# 8bitPig-PigstyGates-FrontPCB.net
KiCad netlist of a schematic drawn in EAGLE
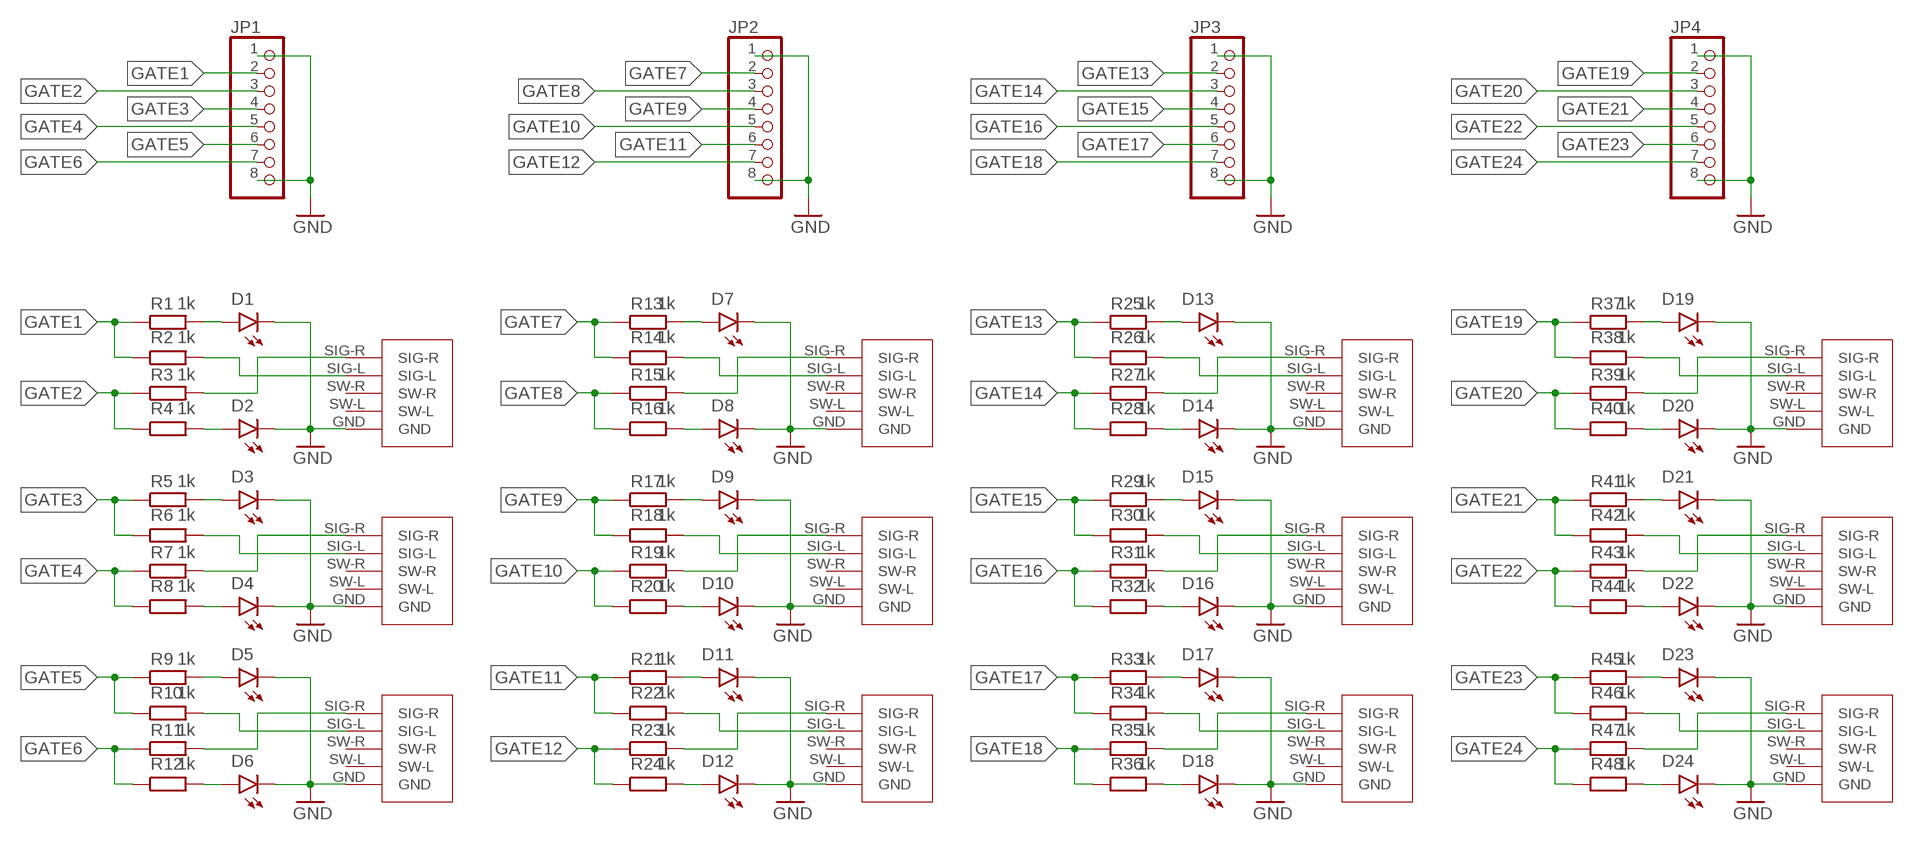
[diagram p0: schematic, sheet 1]

(export (version "E")
  (design (tool "Eeschema 10.0.6"))
  (components
    (comp (ref "D1")
      (value "LED3MM")
      (footprint "eagle-import:LED_3MM")
      (libsource (lib "eagle-import") (part "LED3MM"))
    )
    (comp (ref "D2")
      (value "LED3MM")
      (footprint "eagle-import:LED_3MM")
      (libsource (lib "eagle-import") (part "LED3MM"))
    )
    (comp (ref "D3")
      (value "LED3MM")
      (footprint "eagle-import:LED_3MM")
      (libsource (lib "eagle-import") (part "LED3MM"))
    )
    (comp (ref "D4")
      (value "LED3MM")
      (footprint "eagle-import:LED_3MM")
      (libsource (lib "eagle-import") (part "LED3MM"))
    )
    (comp (ref "D5")
      (value "LED3MM")
      (footprint "eagle-import:LED_3MM")
      (libsource (lib "eagle-import") (part "LED3MM"))
    )
    (comp (ref "D6")
      (value "LED3MM")
      (footprint "eagle-import:LED_3MM")
      (libsource (lib "eagle-import") (part "LED3MM"))
    )
    (comp (ref "D7")
      (value "LED3MM")
      (footprint "eagle-import:LED_3MM")
      (libsource (lib "eagle-import") (part "LED3MM"))
    )
    (comp (ref "D8")
      (value "LED3MM")
      (footprint "eagle-import:LED_3MM")
      (libsource (lib "eagle-import") (part "LED3MM"))
    )
    (comp (ref "D9")
      (value "LED3MM")
      (footprint "eagle-import:LED_3MM")
      (libsource (lib "eagle-import") (part "LED3MM"))
    )
    (comp (ref "D10")
      (value "LED3MM")
      (footprint "eagle-import:LED_3MM")
      (libsource (lib "eagle-import") (part "LED3MM"))
    )
    (comp (ref "D11")
      (value "LED3MM")
      (footprint "eagle-import:LED_3MM")
      (libsource (lib "eagle-import") (part "LED3MM"))
    )
    (comp (ref "D12")
      (value "LED3MM")
      (footprint "eagle-import:LED_3MM")
      (libsource (lib "eagle-import") (part "LED3MM"))
    )
    (comp (ref "D13")
      (value "LED3MM")
      (footprint "eagle-import:LED_3MM")
      (libsource (lib "eagle-import") (part "LED3MM"))
    )
    (comp (ref "D14")
      (value "LED3MM")
      (footprint "eagle-import:LED_3MM")
      (libsource (lib "eagle-import") (part "LED3MM"))
    )
    (comp (ref "D15")
      (value "LED3MM")
      (footprint "eagle-import:LED_3MM")
      (libsource (lib "eagle-import") (part "LED3MM"))
    )
    (comp (ref "D16")
      (value "LED3MM")
      (footprint "eagle-import:LED_3MM")
      (libsource (lib "eagle-import") (part "LED3MM"))
    )
    (comp (ref "D17")
      (value "LED3MM")
      (footprint "eagle-import:LED_3MM")
      (libsource (lib "eagle-import") (part "LED3MM"))
    )
    (comp (ref "D18")
      (value "LED3MM")
      (footprint "eagle-import:LED_3MM")
      (libsource (lib "eagle-import") (part "LED3MM"))
    )
    (comp (ref "D19")
      (value "LED3MM")
      (footprint "eagle-import:LED_3MM")
      (libsource (lib "eagle-import") (part "LED3MM"))
    )
    (comp (ref "D20")
      (value "LED3MM")
      (footprint "eagle-import:LED_3MM")
      (libsource (lib "eagle-import") (part "LED3MM"))
    )
    (comp (ref "D21")
      (value "LED3MM")
      (footprint "eagle-import:LED_3MM")
      (libsource (lib "eagle-import") (part "LED3MM"))
    )
    (comp (ref "D22")
      (value "LED3MM")
      (footprint "eagle-import:LED_3MM")
      (libsource (lib "eagle-import") (part "LED3MM"))
    )
    (comp (ref "D23")
      (value "LED3MM")
      (footprint "eagle-import:LED_3MM")
      (libsource (lib "eagle-import") (part "LED3MM"))
    )
    (comp (ref "D24")
      (value "LED3MM")
      (footprint "eagle-import:LED_3MM")
      (libsource (lib "eagle-import") (part "LED3MM"))
    )
    (comp (ref "DUAL_JACK_1")
      (value "DUAL_MONO_THONKICONN")
      (footprint "eagle-import:DUAL_THONKICONN_MONO")
      (libsource (lib "eagle-import") (part "DUAL_MONO_THONKICONN"))
    )
    (comp (ref "DUAL_JACK_2")
      (value "DUAL_MONO_THONKICONN")
      (footprint "eagle-import:DUAL_THONKICONN_MONO")
      (libsource (lib "eagle-import") (part "DUAL_MONO_THONKICONN"))
    )
    (comp (ref "DUAL_JACK_3")
      (value "DUAL_MONO_THONKICONN")
      (footprint "eagle-import:DUAL_THONKICONN_MONO")
      (libsource (lib "eagle-import") (part "DUAL_MONO_THONKICONN"))
    )
    (comp (ref "DUAL_JACK_4")
      (value "DUAL_MONO_THONKICONN")
      (footprint "eagle-import:DUAL_THONKICONN_MONO")
      (libsource (lib "eagle-import") (part "DUAL_MONO_THONKICONN"))
    )
    (comp (ref "DUAL_JACK_5")
      (value "DUAL_MONO_THONKICONN")
      (footprint "eagle-import:DUAL_THONKICONN_MONO")
      (libsource (lib "eagle-import") (part "DUAL_MONO_THONKICONN"))
    )
    (comp (ref "DUAL_JACK_6")
      (value "DUAL_MONO_THONKICONN")
      (footprint "eagle-import:DUAL_THONKICONN_MONO")
      (libsource (lib "eagle-import") (part "DUAL_MONO_THONKICONN"))
    )
    (comp (ref "DUAL_JACK_7")
      (value "DUAL_MONO_THONKICONN")
      (footprint "eagle-import:DUAL_THONKICONN_MONO")
      (libsource (lib "eagle-import") (part "DUAL_MONO_THONKICONN"))
    )
    (comp (ref "DUAL_JACK_8")
      (value "DUAL_MONO_THONKICONN")
      (footprint "eagle-import:DUAL_THONKICONN_MONO")
      (libsource (lib "eagle-import") (part "DUAL_MONO_THONKICONN"))
    )
    (comp (ref "DUAL_JACK_9")
      (value "DUAL_MONO_THONKICONN")
      (footprint "eagle-import:DUAL_THONKICONN_MONO")
      (libsource (lib "eagle-import") (part "DUAL_MONO_THONKICONN"))
    )
    (comp (ref "DUAL_JACK_10")
      (value "DUAL_MONO_THONKICONN")
      (footprint "eagle-import:DUAL_THONKICONN_MONO")
      (libsource (lib "eagle-import") (part "DUAL_MONO_THONKICONN"))
    )
    (comp (ref "DUAL_JACK_11")
      (value "DUAL_MONO_THONKICONN")
      (footprint "eagle-import:DUAL_THONKICONN_MONO")
      (libsource (lib "eagle-import") (part "DUAL_MONO_THONKICONN"))
    )
    (comp (ref "DUAL_JACK_12")
      (value "DUAL_MONO_THONKICONN")
      (footprint "eagle-import:DUAL_THONKICONN_MONO")
      (libsource (lib "eagle-import") (part "DUAL_MONO_THONKICONN"))
    )
    (comp (ref "JP1")
      (value "PINHD-1X8")
      (footprint "eagle-import:1X08")
      (libsource (lib "eagle-import") (part "PINHD-1X8"))
    )
    (comp (ref "JP2")
      (value "PINHD-1X8")
      (footprint "eagle-import:1X08")
      (libsource (lib "eagle-import") (part "PINHD-1X8"))
    )
    (comp (ref "JP3")
      (value "PINHD-1X8")
      (footprint "eagle-import:1X08")
      (libsource (lib "eagle-import") (part "PINHD-1X8"))
    )
    (comp (ref "JP4")
      (value "PINHD-1X8")
      (footprint "eagle-import:1X08")
      (libsource (lib "eagle-import") (part "PINHD-1X8"))
    )
    (comp (ref "R1")
      (value "1k")
      (footprint "eagle-import:R0603")
      (libsource (lib "eagle-import") (part "R-EU_R0603"))
    )
    (comp (ref "R2")
      (value "1k")
      (footprint "eagle-import:R0603")
      (libsource (lib "eagle-import") (part "R-EU_R0603"))
    )
    (comp (ref "R3")
      (value "1k")
      (footprint "eagle-import:R0603")
      (libsource (lib "eagle-import") (part "R-EU_R0603"))
    )
    (comp (ref "R4")
      (value "1k")
      (footprint "eagle-import:R0603")
      (libsource (lib "eagle-import") (part "R-EU_R0603"))
    )
    (comp (ref "R5")
      (value "1k")
      (footprint "eagle-import:R0603")
      (libsource (lib "eagle-import") (part "R-EU_R0603"))
    )
    (comp (ref "R6")
      (value "1k")
      (footprint "eagle-import:R0603")
      (libsource (lib "eagle-import") (part "R-EU_R0603"))
    )
    (comp (ref "R7")
      (value "1k")
      (footprint "eagle-import:R0603")
      (libsource (lib "eagle-import") (part "R-EU_R0603"))
    )
    (comp (ref "R8")
      (value "1k")
      (footprint "eagle-import:R0603")
      (libsource (lib "eagle-import") (part "R-EU_R0603"))
    )
    (comp (ref "R9")
      (value "1k")
      (footprint "eagle-import:R0603")
      (libsource (lib "eagle-import") (part "R-EU_R0603"))
    )
    (comp (ref "R10")
      (value "1k")
      (footprint "eagle-import:R0603")
      (libsource (lib "eagle-import") (part "R-EU_R0603"))
    )
    (comp (ref "R11")
      (value "1k")
      (footprint "eagle-import:R0603")
      (libsource (lib "eagle-import") (part "R-EU_R0603"))
    )
    (comp (ref "R12")
      (value "1k")
      (footprint "eagle-import:R0603")
      (libsource (lib "eagle-import") (part "R-EU_R0603"))
    )
    (comp (ref "R13")
      (value "1k")
      (footprint "eagle-import:R0603")
      (libsource (lib "eagle-import") (part "R-EU_R0603"))
    )
    (comp (ref "R14")
      (value "1k")
      (footprint "eagle-import:R0603")
      (libsource (lib "eagle-import") (part "R-EU_R0603"))
    )
    (comp (ref "R15")
      (value "1k")
      (footprint "eagle-import:R0603")
      (libsource (lib "eagle-import") (part "R-EU_R0603"))
    )
    (comp (ref "R16")
      (value "1k")
      (footprint "eagle-import:R0603")
      (libsource (lib "eagle-import") (part "R-EU_R0603"))
    )
    (comp (ref "R17")
      (value "1k")
      (footprint "eagle-import:R0603")
      (libsource (lib "eagle-import") (part "R-EU_R0603"))
    )
    (comp (ref "R18")
      (value "1k")
      (footprint "eagle-import:R0603")
      (libsource (lib "eagle-import") (part "R-EU_R0603"))
    )
    (comp (ref "R19")
      (value "1k")
      (footprint "eagle-import:R0603")
      (libsource (lib "eagle-import") (part "R-EU_R0603"))
    )
    (comp (ref "R20")
      (value "1k")
      (footprint "eagle-import:R0603")
      (libsource (lib "eagle-import") (part "R-EU_R0603"))
    )
    (comp (ref "R21")
      (value "1k")
      (footprint "eagle-import:R0603")
      (libsource (lib "eagle-import") (part "R-EU_R0603"))
    )
    (comp (ref "R22")
      (value "1k")
      (footprint "eagle-import:R0603")
      (libsource (lib "eagle-import") (part "R-EU_R0603"))
    )
    (comp (ref "R23")
      (value "1k")
      (footprint "eagle-import:R0603")
      (libsource (lib "eagle-import") (part "R-EU_R0603"))
    )
    (comp (ref "R24")
      (value "1k")
      (footprint "eagle-import:R0603")
      (libsource (lib "eagle-import") (part "R-EU_R0603"))
    )
    (comp (ref "R25")
      (value "1k")
      (footprint "eagle-import:R0603")
      (libsource (lib "eagle-import") (part "R-EU_R0603"))
    )
    (comp (ref "R26")
      (value "1k")
      (footprint "eagle-import:R0603")
      (libsource (lib "eagle-import") (part "R-EU_R0603"))
    )
    (comp (ref "R27")
      (value "1k")
      (footprint "eagle-import:R0603")
      (libsource (lib "eagle-import") (part "R-EU_R0603"))
    )
    (comp (ref "R28")
      (value "1k")
      (footprint "eagle-import:R0603")
      (libsource (lib "eagle-import") (part "R-EU_R0603"))
    )
    (comp (ref "R29")
      (value "1k")
      (footprint "eagle-import:R0603")
      (libsource (lib "eagle-import") (part "R-EU_R0603"))
    )
    (comp (ref "R30")
      (value "1k")
      (footprint "eagle-import:R0603")
      (libsource (lib "eagle-import") (part "R-EU_R0603"))
    )
    (comp (ref "R31")
      (value "1k")
      (footprint "eagle-import:R0603")
      (libsource (lib "eagle-import") (part "R-EU_R0603"))
    )
    (comp (ref "R32")
      (value "1k")
      (footprint "eagle-import:R0603")
      (libsource (lib "eagle-import") (part "R-EU_R0603"))
    )
    (comp (ref "R33")
      (value "1k")
      (footprint "eagle-import:R0603")
      (libsource (lib "eagle-import") (part "R-EU_R0603"))
    )
    (comp (ref "R34")
      (value "1k")
      (footprint "eagle-import:R0603")
      (libsource (lib "eagle-import") (part "R-EU_R0603"))
    )
    (comp (ref "R35")
      (value "1k")
      (footprint "eagle-import:R0603")
      (libsource (lib "eagle-import") (part "R-EU_R0603"))
    )
    (comp (ref "R36")
      (value "1k")
      (footprint "eagle-import:R0603")
      (libsource (lib "eagle-import") (part "R-EU_R0603"))
    )
    (comp (ref "R37")
      (value "1k")
      (footprint "eagle-import:R0603")
      (libsource (lib "eagle-import") (part "R-EU_R0603"))
    )
    (comp (ref "R38")
      (value "1k")
      (footprint "eagle-import:R0603")
      (libsource (lib "eagle-import") (part "R-EU_R0603"))
    )
    (comp (ref "R39")
      (value "1k")
      (footprint "eagle-import:R0603")
      (libsource (lib "eagle-import") (part "R-EU_R0603"))
    )
    (comp (ref "R40")
      (value "1k")
      (footprint "eagle-import:R0603")
      (libsource (lib "eagle-import") (part "R-EU_R0603"))
    )
    (comp (ref "R41")
      (value "1k")
      (footprint "eagle-import:R0603")
      (libsource (lib "eagle-import") (part "R-EU_R0603"))
    )
    (comp (ref "R42")
      (value "1k")
      (footprint "eagle-import:R0603")
      (libsource (lib "eagle-import") (part "R-EU_R0603"))
    )
    (comp (ref "R43")
      (value "1k")
      (footprint "eagle-import:R0603")
      (libsource (lib "eagle-import") (part "R-EU_R0603"))
    )
    (comp (ref "R44")
      (value "1k")
      (footprint "eagle-import:R0603")
      (libsource (lib "eagle-import") (part "R-EU_R0603"))
    )
    (comp (ref "R45")
      (value "1k")
      (footprint "eagle-import:R0603")
      (libsource (lib "eagle-import") (part "R-EU_R0603"))
    )
    (comp (ref "R46")
      (value "1k")
      (footprint "eagle-import:R0603")
      (libsource (lib "eagle-import") (part "R-EU_R0603"))
    )
    (comp (ref "R47")
      (value "1k")
      (footprint "eagle-import:R0603")
      (libsource (lib "eagle-import") (part "R-EU_R0603"))
    )
    (comp (ref "R48")
      (value "1k")
      (footprint "eagle-import:R0603")
      (libsource (lib "eagle-import") (part "R-EU_R0603"))
    )
  )
  (nets
    (net (code "1") (name "GATE1") (class "Default")
      (node (ref "JP1") (pin "2") (pinfunction "2_2") (pintype "passive"))
      (node (ref "R1") (pin "1") (pinfunction "1_1") (pintype "passive"))
      (node (ref "R2") (pin "1") (pinfunction "1_1") (pintype "passive"))
    )
    (net (code "2") (name "GATE2") (class "Default")
      (node (ref "JP1") (pin "3") (pinfunction "3_3") (pintype "passive"))
      (node (ref "R3") (pin "1") (pinfunction "1_1") (pintype "passive"))
      (node (ref "R4") (pin "1") (pinfunction "1_1") (pintype "passive"))
    )
    (net (code "3") (name "GATE3") (class "Default")
      (node (ref "JP1") (pin "4") (pinfunction "4_4") (pintype "passive"))
      (node (ref "R5") (pin "1") (pinfunction "1_1") (pintype "passive"))
      (node (ref "R6") (pin "1") (pinfunction "1_1") (pintype "passive"))
    )
    (net (code "4") (name "GATE4") (class "Default")
      (node (ref "JP1") (pin "5") (pinfunction "5_5") (pintype "passive"))
      (node (ref "R7") (pin "1") (pinfunction "1_1") (pintype "passive"))
      (node (ref "R8") (pin "1") (pinfunction "1_1") (pintype "passive"))
    )
    (net (code "5") (name "GATE5") (class "Default")
      (node (ref "JP1") (pin "6") (pinfunction "6_6") (pintype "passive"))
      (node (ref "R10") (pin "1") (pinfunction "1_1") (pintype "passive"))
      (node (ref "R9") (pin "1") (pinfunction "1_1") (pintype "passive"))
    )
    (net (code "6") (name "GATE6") (class "Default")
      (node (ref "JP1") (pin "7") (pinfunction "7_7") (pintype "passive"))
      (node (ref "R11") (pin "1") (pinfunction "1_1") (pintype "passive"))
      (node (ref "R12") (pin "1") (pinfunction "1_1") (pintype "passive"))
    )
    (net (code "7") (name "GATE7") (class "Default")
      (node (ref "JP2") (pin "2") (pinfunction "2_2") (pintype "passive"))
      (node (ref "R13") (pin "1") (pinfunction "1_1") (pintype "passive"))
      (node (ref "R14") (pin "1") (pinfunction "1_1") (pintype "passive"))
    )
    (net (code "8") (name "GATE8") (class "Default")
      (node (ref "JP2") (pin "3") (pinfunction "3_3") (pintype "passive"))
      (node (ref "R15") (pin "1") (pinfunction "1_1") (pintype "passive"))
      (node (ref "R16") (pin "1") (pinfunction "1_1") (pintype "passive"))
    )
    (net (code "9") (name "GATE9") (class "Default")
      (node (ref "JP2") (pin "4") (pinfunction "4_4") (pintype "passive"))
      (node (ref "R17") (pin "1") (pinfunction "1_1") (pintype "passive"))
      (node (ref "R18") (pin "1") (pinfunction "1_1") (pintype "passive"))
    )
    (net (code "10") (name "GATE10") (class "Default")
      (node (ref "JP2") (pin "5") (pinfunction "5_5") (pintype "passive"))
      (node (ref "R19") (pin "1") (pinfunction "1_1") (pintype "passive"))
      (node (ref "R20") (pin "1") (pinfunction "1_1") (pintype "passive"))
    )
    (net (code "11") (name "GATE11") (class "Default")
      (node (ref "JP2") (pin "6") (pinfunction "6_6") (pintype "passive"))
      (node (ref "R21") (pin "1") (pinfunction "1_1") (pintype "passive"))
      (node (ref "R22") (pin "1") (pinfunction "1_1") (pintype "passive"))
    )
    (net (code "12") (name "GATE12") (class "Default")
      (node (ref "JP2") (pin "7") (pinfunction "7_7") (pintype "passive"))
      (node (ref "R23") (pin "1") (pinfunction "1_1") (pintype "passive"))
      (node (ref "R24") (pin "1") (pinfunction "1_1") (pintype "passive"))
    )
    (net (code "13") (name "GATE13") (class "Default")
      (node (ref "JP3") (pin "2") (pinfunction "2_2") (pintype "passive"))
      (node (ref "R25") (pin "1") (pinfunction "1_1") (pintype "passive"))
      (node (ref "R26") (pin "1") (pinfunction "1_1") (pintype "passive"))
    )
    (net (code "14") (name "GATE14") (class "Default")
      (node (ref "JP3") (pin "3") (pinfunction "3_3") (pintype "passive"))
      (node (ref "R27") (pin "1") (pinfunction "1_1") (pintype "passive"))
      (node (ref "R28") (pin "1") (pinfunction "1_1") (pintype "passive"))
    )
    (net (code "15") (name "GATE15") (class "Default")
      (node (ref "JP3") (pin "4") (pinfunction "4_4") (pintype "passive"))
      (node (ref "R29") (pin "1") (pinfunction "1_1") (pintype "passive"))
      (node (ref "R30") (pin "1") (pinfunction "1_1") (pintype "passive"))
    )
    (net (code "16") (name "GATE16") (class "Default")
      (node (ref "JP3") (pin "5") (pinfunction "5_5") (pintype "passive"))
      (node (ref "R31") (pin "1") (pinfunction "1_1") (pintype "passive"))
      (node (ref "R32") (pin "1") (pinfunction "1_1") (pintype "passive"))
    )
    (net (code "17") (name "GATE17") (class "Default")
      (node (ref "JP3") (pin "6") (pinfunction "6_6") (pintype "passive"))
      (node (ref "R33") (pin "1") (pinfunction "1_1") (pintype "passive"))
      (node (ref "R34") (pin "1") (pinfunction "1_1") (pintype "passive"))
    )
    (net (code "18") (name "GATE18") (class "Default")
      (node (ref "JP3") (pin "7") (pinfunction "7_7") (pintype "passive"))
      (node (ref "R35") (pin "1") (pinfunction "1_1") (pintype "passive"))
      (node (ref "R36") (pin "1") (pinfunction "1_1") (pintype "passive"))
    )
    (net (code "19") (name "GATE19") (class "Default")
      (node (ref "JP4") (pin "2") (pinfunction "2_2") (pintype "passive"))
      (node (ref "R37") (pin "1") (pinfunction "1_1") (pintype "passive"))
      (node (ref "R38") (pin "1") (pinfunction "1_1") (pintype "passive"))
    )
    (net (code "20") (name "GATE20") (class "Default")
      (node (ref "JP4") (pin "3") (pinfunction "3_3") (pintype "passive"))
      (node (ref "R39") (pin "1") (pinfunction "1_1") (pintype "passive"))
      (node (ref "R40") (pin "1") (pinfunction "1_1") (pintype "passive"))
    )
    (net (code "21") (name "GATE21") (class "Default")
      (node (ref "JP4") (pin "4") (pinfunction "4_4") (pintype "passive"))
      (node (ref "R41") (pin "1") (pinfunction "1_1") (pintype "passive"))
      (node (ref "R42") (pin "1") (pinfunction "1_1") (pintype "passive"))
    )
    (net (code "22") (name "GATE22") (class "Default")
      (node (ref "JP4") (pin "5") (pinfunction "5_5") (pintype "passive"))
      (node (ref "R43") (pin "1") (pinfunction "1_1") (pintype "passive"))
      (node (ref "R44") (pin "1") (pinfunction "1_1") (pintype "passive"))
    )
    (net (code "23") (name "GATE23") (class "Default")
      (node (ref "JP4") (pin "6") (pinfunction "6_6") (pintype "passive"))
      (node (ref "R45") (pin "1") (pinfunction "1_1") (pintype "passive"))
      (node (ref "R46") (pin "1") (pinfunction "1_1") (pintype "passive"))
    )
    (net (code "24") (name "GATE24") (class "Default")
      (node (ref "JP4") (pin "7") (pinfunction "7_7") (pintype "passive"))
      (node (ref "R47") (pin "1") (pinfunction "1_1") (pintype "passive"))
      (node (ref "R48") (pin "1") (pinfunction "1_1") (pintype "passive"))
    )
    (net (code "25") (name "GND") (class "Default")
      (node (ref "D1") (pin "K") (pinfunction "C_K") (pintype "passive"))
      (node (ref "D10") (pin "K") (pinfunction "C_K") (pintype "passive"))
      (node (ref "D11") (pin "K") (pinfunction "C_K") (pintype "passive"))
      (node (ref "D12") (pin "K") (pinfunction "C_K") (pintype "passive"))
      (node (ref "D13") (pin "K") (pinfunction "C_K") (pintype "passive"))
      (node (ref "D14") (pin "K") (pinfunction "C_K") (pintype "passive"))
      (node (ref "D15") (pin "K") (pinfunction "C_K") (pintype "passive"))
      (node (ref "D16") (pin "K") (pinfunction "C_K") (pintype "passive"))
      (node (ref "D17") (pin "K") (pinfunction "C_K") (pintype "passive"))
      (node (ref "D18") (pin "K") (pinfunction "C_K") (pintype "passive"))
      (node (ref "D19") (pin "K") (pinfunction "C_K") (pintype "passive"))
      (node (ref "D2") (pin "K") (pinfunction "C_K") (pintype "passive"))
      (node (ref "D20") (pin "K") (pinfunction "C_K") (pintype "passive"))
      (node (ref "D21") (pin "K") (pinfunction "C_K") (pintype "passive"))
      (node (ref "D22") (pin "K") (pinfunction "C_K") (pintype "passive"))
      (node (ref "D23") (pin "K") (pinfunction "C_K") (pintype "passive"))
      (node (ref "D24") (pin "K") (pinfunction "C_K") (pintype "passive"))
      (node (ref "D3") (pin "K") (pinfunction "C_K") (pintype "passive"))
      (node (ref "D4") (pin "K") (pinfunction "C_K") (pintype "passive"))
      (node (ref "D5") (pin "K") (pinfunction "C_K") (pintype "passive"))
      (node (ref "D6") (pin "K") (pinfunction "C_K") (pintype "passive"))
      (node (ref "D7") (pin "K") (pinfunction "C_K") (pintype "passive"))
      (node (ref "D8") (pin "K") (pinfunction "C_K") (pintype "passive"))
      (node (ref "D9") (pin "K") (pinfunction "C_K") (pintype "passive"))
      (node (ref "DUAL_JACK_1") (pin "GND") (pinfunction "GND_GND") (pintype "bidirectional"))
      (node (ref "DUAL_JACK_10") (pin "GND") (pinfunction "GND_GND") (pintype "bidirectional"))
      (node (ref "DUAL_JACK_11") (pin "GND") (pinfunction "GND_GND") (pintype "bidirectional"))
      (node (ref "DUAL_JACK_12") (pin "GND") (pinfunction "GND_GND") (pintype "bidirectional"))
      (node (ref "DUAL_JACK_2") (pin "GND") (pinfunction "GND_GND") (pintype "bidirectional"))
      (node (ref "DUAL_JACK_3") (pin "GND") (pinfunction "GND_GND") (pintype "bidirectional"))
      (node (ref "DUAL_JACK_4") (pin "GND") (pinfunction "GND_GND") (pintype "bidirectional"))
      (node (ref "DUAL_JACK_5") (pin "GND") (pinfunction "GND_GND") (pintype "bidirectional"))
      (node (ref "DUAL_JACK_6") (pin "GND") (pinfunction "GND_GND") (pintype "bidirectional"))
      (node (ref "DUAL_JACK_7") (pin "GND") (pinfunction "GND_GND") (pintype "bidirectional"))
      (node (ref "DUAL_JACK_8") (pin "GND") (pinfunction "GND_GND") (pintype "bidirectional"))
      (node (ref "DUAL_JACK_9") (pin "GND") (pinfunction "GND_GND") (pintype "bidirectional"))
      (node (ref "JP1") (pin "1") (pinfunction "1_1") (pintype "passive"))
      (node (ref "JP1") (pin "8") (pinfunction "8_8") (pintype "passive"))
      (node (ref "JP2") (pin "1") (pinfunction "1_1") (pintype "passive"))
      (node (ref "JP2") (pin "8") (pinfunction "8_8") (pintype "passive"))
      (node (ref "JP3") (pin "1") (pinfunction "1_1") (pintype "passive"))
      (node (ref "JP3") (pin "8") (pinfunction "8_8") (pintype "passive"))
      (node (ref "JP4") (pin "1") (pinfunction "1_1") (pintype "passive"))
      (node (ref "JP4") (pin "8") (pinfunction "8_8") (pintype "passive"))
    )
    (net (code "26") (name "Net-(D1-PadA)") (class "Default")
      (node (ref "D1") (pin "A") (pinfunction "A_A") (pintype "passive"))
      (node (ref "R1") (pin "2") (pinfunction "2_2") (pintype "passive"))
    )
    (net (code "27") (name "Net-(D2-PadA)") (class "Default")
      (node (ref "D2") (pin "A") (pinfunction "A_A") (pintype "passive"))
      (node (ref "R4") (pin "2") (pinfunction "2_2") (pintype "passive"))
    )
    (net (code "28") (name "Net-(D3-PadA)") (class "Default")
      (node (ref "D3") (pin "A") (pinfunction "A_A") (pintype "passive"))
      (node (ref "R5") (pin "2") (pinfunction "2_2") (pintype "passive"))
    )
    (net (code "29") (name "Net-(D4-PadA)") (class "Default")
      (node (ref "D4") (pin "A") (pinfunction "A_A") (pintype "passive"))
      (node (ref "R8") (pin "2") (pinfunction "2_2") (pintype "passive"))
    )
    (net (code "30") (name "Net-(D5-PadA)") (class "Default")
      (node (ref "D5") (pin "A") (pinfunction "A_A") (pintype "passive"))
      (node (ref "R9") (pin "2") (pinfunction "2_2") (pintype "passive"))
    )
    (net (code "31") (name "Net-(D6-PadA)") (class "Default")
      (node (ref "D6") (pin "A") (pinfunction "A_A") (pintype "passive"))
      (node (ref "R12") (pin "2") (pinfunction "2_2") (pintype "passive"))
    )
    (net (code "32") (name "Net-(D7-PadA)") (class "Default")
      (node (ref "D7") (pin "A") (pinfunction "A_A") (pintype "passive"))
      (node (ref "R13") (pin "2") (pinfunction "2_2") (pintype "passive"))
    )
    (net (code "33") (name "Net-(D8-PadA)") (class "Default")
      (node (ref "D8") (pin "A") (pinfunction "A_A") (pintype "passive"))
      (node (ref "R16") (pin "2") (pinfunction "2_2") (pintype "passive"))
    )
    (net (code "34") (name "Net-(D9-PadA)") (class "Default")
      (node (ref "D9") (pin "A") (pinfunction "A_A") (pintype "passive"))
      (node (ref "R17") (pin "2") (pinfunction "2_2") (pintype "passive"))
    )
    (net (code "35") (name "Net-(D10-PadA)") (class "Default")
      (node (ref "D10") (pin "A") (pinfunction "A_A") (pintype "passive"))
      (node (ref "R20") (pin "2") (pinfunction "2_2") (pintype "passive"))
    )
    (net (code "36") (name "Net-(D11-PadA)") (class "Default")
      (node (ref "D11") (pin "A") (pinfunction "A_A") (pintype "passive"))
      (node (ref "R21") (pin "2") (pinfunction "2_2") (pintype "passive"))
    )
    (net (code "37") (name "Net-(D12-PadA)") (class "Default")
      (node (ref "D12") (pin "A") (pinfunction "A_A") (pintype "passive"))
      (node (ref "R24") (pin "2") (pinfunction "2_2") (pintype "passive"))
    )
    (net (code "38") (name "Net-(D13-PadA)") (class "Default")
      (node (ref "D13") (pin "A") (pinfunction "A_A") (pintype "passive"))
      (node (ref "R25") (pin "2") (pinfunction "2_2") (pintype "passive"))
    )
    (net (code "39") (name "Net-(D14-PadA)") (class "Default")
      (node (ref "D14") (pin "A") (pinfunction "A_A") (pintype "passive"))
      (node (ref "R28") (pin "2") (pinfunction "2_2") (pintype "passive"))
    )
    (net (code "40") (name "Net-(D15-PadA)") (class "Default")
      (node (ref "D15") (pin "A") (pinfunction "A_A") (pintype "passive"))
      (node (ref "R29") (pin "2") (pinfunction "2_2") (pintype "passive"))
    )
    (net (code "41") (name "Net-(D16-PadA)") (class "Default")
      (node (ref "D16") (pin "A") (pinfunction "A_A") (pintype "passive"))
      (node (ref "R32") (pin "2") (pinfunction "2_2") (pintype "passive"))
    )
    (net (code "42") (name "Net-(D17-PadA)") (class "Default")
      (node (ref "D17") (pin "A") (pinfunction "A_A") (pintype "passive"))
      (node (ref "R33") (pin "2") (pinfunction "2_2") (pintype "passive"))
    )
    (net (code "43") (name "Net-(D18-PadA)") (class "Default")
      (node (ref "D18") (pin "A") (pinfunction "A_A") (pintype "passive"))
      (node (ref "R36") (pin "2") (pinfunction "2_2") (pintype "passive"))
    )
    (net (code "44") (name "Net-(D19-PadA)") (class "Default")
      (node (ref "D19") (pin "A") (pinfunction "A_A") (pintype "passive"))
      (node (ref "R37") (pin "2") (pinfunction "2_2") (pintype "passive"))
    )
    (net (code "45") (name "Net-(D20-PadA)") (class "Default")
      (node (ref "D20") (pin "A") (pinfunction "A_A") (pintype "passive"))
      (node (ref "R40") (pin "2") (pinfunction "2_2") (pintype "passive"))
    )
    (net (code "46") (name "Net-(D21-PadA)") (class "Default")
      (node (ref "D21") (pin "A") (pinfunction "A_A") (pintype "passive"))
      (node (ref "R41") (pin "2") (pinfunction "2_2") (pintype "passive"))
    )
    (net (code "47") (name "Net-(D22-PadA)") (class "Default")
      (node (ref "D22") (pin "A") (pinfunction "A_A") (pintype "passive"))
      (node (ref "R44") (pin "2") (pinfunction "2_2") (pintype "passive"))
    )
    (net (code "48") (name "Net-(D23-PadA)") (class "Default")
      (node (ref "D23") (pin "A") (pinfunction "A_A") (pintype "passive"))
      (node (ref "R45") (pin "2") (pinfunction "2_2") (pintype "passive"))
    )
    (net (code "49") (name "Net-(D24-PadA)") (class "Default")
      (node (ref "D24") (pin "A") (pinfunction "A_A") (pintype "passive"))
      (node (ref "R48") (pin "2") (pinfunction "2_2") (pintype "passive"))
    )
    (net (code "50") (name "Net-(DUAL_JACK_1-PadSIG-L)") (class "Default")
      (node (ref "DUAL_JACK_1") (pin "SIG-L") (pinfunction "SIG-L_SIG-L") (pintype "bidirectional"))
      (node (ref "R2") (pin "2") (pinfunction "2_2") (pintype "passive"))
    )
    (net (code "51") (name "Net-(DUAL_JACK_1-PadSIG-R)") (class "Default")
      (node (ref "DUAL_JACK_1") (pin "SIG-R") (pinfunction "SIG-R_SIG-R") (pintype "bidirectional"))
      (node (ref "R3") (pin "2") (pinfunction "2_2") (pintype "passive"))
    )
    (net (code "52") (name "Net-(DUAL_JACK_2-PadSIG-L)") (class "Default")
      (node (ref "DUAL_JACK_2") (pin "SIG-L") (pinfunction "SIG-L_SIG-L") (pintype "bidirectional"))
      (node (ref "R6") (pin "2") (pinfunction "2_2") (pintype "passive"))
    )
    (net (code "53") (name "Net-(DUAL_JACK_2-PadSIG-R)") (class "Default")
      (node (ref "DUAL_JACK_2") (pin "SIG-R") (pinfunction "SIG-R_SIG-R") (pintype "bidirectional"))
      (node (ref "R7") (pin "2") (pinfunction "2_2") (pintype "passive"))
    )
    (net (code "54") (name "Net-(DUAL_JACK_3-PadSIG-L)") (class "Default")
      (node (ref "DUAL_JACK_3") (pin "SIG-L") (pinfunction "SIG-L_SIG-L") (pintype "bidirectional"))
      (node (ref "R10") (pin "2") (pinfunction "2_2") (pintype "passive"))
    )
    (net (code "55") (name "Net-(DUAL_JACK_3-PadSIG-R)") (class "Default")
      (node (ref "DUAL_JACK_3") (pin "SIG-R") (pinfunction "SIG-R_SIG-R") (pintype "bidirectional"))
      (node (ref "R11") (pin "2") (pinfunction "2_2") (pintype "passive"))
    )
    (net (code "56") (name "Net-(DUAL_JACK_4-PadSIG-L)") (class "Default")
      (node (ref "DUAL_JACK_4") (pin "SIG-L") (pinfunction "SIG-L_SIG-L") (pintype "bidirectional"))
      (node (ref "R14") (pin "2") (pinfunction "2_2") (pintype "passive"))
    )
    (net (code "57") (name "Net-(DUAL_JACK_4-PadSIG-R)") (class "Default")
      (node (ref "DUAL_JACK_4") (pin "SIG-R") (pinfunction "SIG-R_SIG-R") (pintype "bidirectional"))
      (node (ref "R15") (pin "2") (pinfunction "2_2") (pintype "passive"))
    )
    (net (code "58") (name "Net-(DUAL_JACK_5-PadSIG-L)") (class "Default")
      (node (ref "DUAL_JACK_5") (pin "SIG-L") (pinfunction "SIG-L_SIG-L") (pintype "bidirectional"))
      (node (ref "R18") (pin "2") (pinfunction "2_2") (pintype "passive"))
    )
    (net (code "59") (name "Net-(DUAL_JACK_5-PadSIG-R)") (class "Default")
      (node (ref "DUAL_JACK_5") (pin "SIG-R") (pinfunction "SIG-R_SIG-R") (pintype "bidirectional"))
      (node (ref "R19") (pin "2") (pinfunction "2_2") (pintype "passive"))
    )
    (net (code "60") (name "Net-(DUAL_JACK_6-PadSIG-L)") (class "Default")
      (node (ref "DUAL_JACK_6") (pin "SIG-L") (pinfunction "SIG-L_SIG-L") (pintype "bidirectional"))
      (node (ref "R22") (pin "2") (pinfunction "2_2") (pintype "passive"))
    )
    (net (code "61") (name "Net-(DUAL_JACK_6-PadSIG-R)") (class "Default")
      (node (ref "DUAL_JACK_6") (pin "SIG-R") (pinfunction "SIG-R_SIG-R") (pintype "bidirectional"))
      (node (ref "R23") (pin "2") (pinfunction "2_2") (pintype "passive"))
    )
    (net (code "62") (name "Net-(DUAL_JACK_7-PadSIG-L)") (class "Default")
      (node (ref "DUAL_JACK_7") (pin "SIG-L") (pinfunction "SIG-L_SIG-L") (pintype "bidirectional"))
      (node (ref "R26") (pin "2") (pinfunction "2_2") (pintype "passive"))
    )
    (net (code "63") (name "Net-(DUAL_JACK_7-PadSIG-R)") (class "Default")
      (node (ref "DUAL_JACK_7") (pin "SIG-R") (pinfunction "SIG-R_SIG-R") (pintype "bidirectional"))
      (node (ref "R27") (pin "2") (pinfunction "2_2") (pintype "passive"))
    )
    (net (code "64") (name "Net-(DUAL_JACK_8-PadSIG-L)") (class "Default")
      (node (ref "DUAL_JACK_8") (pin "SIG-L") (pinfunction "SIG-L_SIG-L") (pintype "bidirectional"))
      (node (ref "R30") (pin "2") (pinfunction "2_2") (pintype "passive"))
    )
    (net (code "65") (name "Net-(DUAL_JACK_8-PadSIG-R)") (class "Default")
      (node (ref "DUAL_JACK_8") (pin "SIG-R") (pinfunction "SIG-R_SIG-R") (pintype "bidirectional"))
      (node (ref "R31") (pin "2") (pinfunction "2_2") (pintype "passive"))
    )
    (net (code "66") (name "Net-(DUAL_JACK_9-PadSIG-L)") (class "Default")
      (node (ref "DUAL_JACK_9") (pin "SIG-L") (pinfunction "SIG-L_SIG-L") (pintype "bidirectional"))
      (node (ref "R34") (pin "2") (pinfunction "2_2") (pintype "passive"))
    )
    (net (code "67") (name "Net-(DUAL_JACK_9-PadSIG-R)") (class "Default")
      (node (ref "DUAL_JACK_9") (pin "SIG-R") (pinfunction "SIG-R_SIG-R") (pintype "bidirectional"))
      (node (ref "R35") (pin "2") (pinfunction "2_2") (pintype "passive"))
    )
    (net (code "68") (name "Net-(DUAL_JACK_10-PadSIG-L)") (class "Default")
      (node (ref "DUAL_JACK_10") (pin "SIG-L") (pinfunction "SIG-L_SIG-L") (pintype "bidirectional"))
      (node (ref "R38") (pin "2") (pinfunction "2_2") (pintype "passive"))
    )
    (net (code "69") (name "Net-(DUAL_JACK_10-PadSIG-R)") (class "Default")
      (node (ref "DUAL_JACK_10") (pin "SIG-R") (pinfunction "SIG-R_SIG-R") (pintype "bidirectional"))
      (node (ref "R39") (pin "2") (pinfunction "2_2") (pintype "passive"))
    )
    (net (code "70") (name "Net-(DUAL_JACK_11-PadSIG-L)") (class "Default")
      (node (ref "DUAL_JACK_11") (pin "SIG-L") (pinfunction "SIG-L_SIG-L") (pintype "bidirectional"))
      (node (ref "R42") (pin "2") (pinfunction "2_2") (pintype "passive"))
    )
    (net (code "71") (name "Net-(DUAL_JACK_11-PadSIG-R)") (class "Default")
      (node (ref "DUAL_JACK_11") (pin "SIG-R") (pinfunction "SIG-R_SIG-R") (pintype "bidirectional"))
      (node (ref "R43") (pin "2") (pinfunction "2_2") (pintype "passive"))
    )
    (net (code "72") (name "Net-(DUAL_JACK_12-PadSIG-L)") (class "Default")
      (node (ref "DUAL_JACK_12") (pin "SIG-L") (pinfunction "SIG-L_SIG-L") (pintype "bidirectional"))
      (node (ref "R46") (pin "2") (pinfunction "2_2") (pintype "passive"))
    )
    (net (code "73") (name "Net-(DUAL_JACK_12-PadSIG-R)") (class "Default")
      (node (ref "DUAL_JACK_12") (pin "SIG-R") (pinfunction "SIG-R_SIG-R") (pintype "bidirectional"))
      (node (ref "R47") (pin "2") (pinfunction "2_2") (pintype "passive"))
    )
    (net (code "74") (name "unconnected-(DUAL_JACK_1-PadSW-L)") (class "Default")
      (node (ref "DUAL_JACK_1") (pin "SW-L") (pinfunction "SW-L_SW-L") (pintype "bidirectional"))
    )
    (net (code "75") (name "unconnected-(DUAL_JACK_1-PadSW-R)") (class "Default")
      (node (ref "DUAL_JACK_1") (pin "SW-R") (pinfunction "SW-R_SW-R") (pintype "bidirectional"))
    )
    (net (code "76") (name "unconnected-(DUAL_JACK_2-PadSW-L)") (class "Default")
      (node (ref "DUAL_JACK_2") (pin "SW-L") (pinfunction "SW-L_SW-L") (pintype "bidirectional"))
    )
    (net (code "77") (name "unconnected-(DUAL_JACK_2-PadSW-R)") (class "Default")
      (node (ref "DUAL_JACK_2") (pin "SW-R") (pinfunction "SW-R_SW-R") (pintype "bidirectional"))
    )
    (net (code "78") (name "unconnected-(DUAL_JACK_3-PadSW-L)") (class "Default")
      (node (ref "DUAL_JACK_3") (pin "SW-L") (pinfunction "SW-L_SW-L") (pintype "bidirectional"))
    )
    (net (code "79") (name "unconnected-(DUAL_JACK_3-PadSW-R)") (class "Default")
      (node (ref "DUAL_JACK_3") (pin "SW-R") (pinfunction "SW-R_SW-R") (pintype "bidirectional"))
    )
    (net (code "80") (name "unconnected-(DUAL_JACK_4-PadSW-L)") (class "Default")
      (node (ref "DUAL_JACK_4") (pin "SW-L") (pinfunction "SW-L_SW-L") (pintype "bidirectional"))
    )
    (net (code "81") (name "unconnected-(DUAL_JACK_4-PadSW-R)") (class "Default")
      (node (ref "DUAL_JACK_4") (pin "SW-R") (pinfunction "SW-R_SW-R") (pintype "bidirectional"))
    )
    (net (code "82") (name "unconnected-(DUAL_JACK_5-PadSW-L)") (class "Default")
      (node (ref "DUAL_JACK_5") (pin "SW-L") (pinfunction "SW-L_SW-L") (pintype "bidirectional"))
    )
    (net (code "83") (name "unconnected-(DUAL_JACK_5-PadSW-R)") (class "Default")
      (node (ref "DUAL_JACK_5") (pin "SW-R") (pinfunction "SW-R_SW-R") (pintype "bidirectional"))
    )
    (net (code "84") (name "unconnected-(DUAL_JACK_6-PadSW-L)") (class "Default")
      (node (ref "DUAL_JACK_6") (pin "SW-L") (pinfunction "SW-L_SW-L") (pintype "bidirectional"))
    )
    (net (code "85") (name "unconnected-(DUAL_JACK_6-PadSW-R)") (class "Default")
      (node (ref "DUAL_JACK_6") (pin "SW-R") (pinfunction "SW-R_SW-R") (pintype "bidirectional"))
    )
    (net (code "86") (name "unconnected-(DUAL_JACK_7-PadSW-L)") (class "Default")
      (node (ref "DUAL_JACK_7") (pin "SW-L") (pinfunction "SW-L_SW-L") (pintype "bidirectional"))
    )
    (net (code "87") (name "unconnected-(DUAL_JACK_7-PadSW-R)") (class "Default")
      (node (ref "DUAL_JACK_7") (pin "SW-R") (pinfunction "SW-R_SW-R") (pintype "bidirectional"))
    )
    (net (code "88") (name "unconnected-(DUAL_JACK_8-PadSW-L)") (class "Default")
      (node (ref "DUAL_JACK_8") (pin "SW-L") (pinfunction "SW-L_SW-L") (pintype "bidirectional"))
    )
    (net (code "89") (name "unconnected-(DUAL_JACK_8-PadSW-R)") (class "Default")
      (node (ref "DUAL_JACK_8") (pin "SW-R") (pinfunction "SW-R_SW-R") (pintype "bidirectional"))
    )
    (net (code "90") (name "unconnected-(DUAL_JACK_9-PadSW-L)") (class "Default")
      (node (ref "DUAL_JACK_9") (pin "SW-L") (pinfunction "SW-L_SW-L") (pintype "bidirectional"))
    )
    (net (code "91") (name "unconnected-(DUAL_JACK_9-PadSW-R)") (class "Default")
      (node (ref "DUAL_JACK_9") (pin "SW-R") (pinfunction "SW-R_SW-R") (pintype "bidirectional"))
    )
    (net (code "92") (name "unconnected-(DUAL_JACK_10-PadSW-L)") (class "Default")
      (node (ref "DUAL_JACK_10") (pin "SW-L") (pinfunction "SW-L_SW-L") (pintype "bidirectional"))
    )
    (net (code "93") (name "unconnected-(DUAL_JACK_10-PadSW-R)") (class "Default")
      (node (ref "DUAL_JACK_10") (pin "SW-R") (pinfunction "SW-R_SW-R") (pintype "bidirectional"))
    )
    (net (code "94") (name "unconnected-(DUAL_JACK_11-PadSW-L)") (class "Default")
      (node (ref "DUAL_JACK_11") (pin "SW-L") (pinfunction "SW-L_SW-L") (pintype "bidirectional"))
    )
    (net (code "95") (name "unconnected-(DUAL_JACK_11-PadSW-R)") (class "Default")
      (node (ref "DUAL_JACK_11") (pin "SW-R") (pinfunction "SW-R_SW-R") (pintype "bidirectional"))
    )
    (net (code "96") (name "unconnected-(DUAL_JACK_12-PadSW-L)") (class "Default")
      (node (ref "DUAL_JACK_12") (pin "SW-L") (pinfunction "SW-L_SW-L") (pintype "bidirectional"))
    )
    (net (code "97") (name "unconnected-(DUAL_JACK_12-PadSW-R)") (class "Default")
      (node (ref "DUAL_JACK_12") (pin "SW-R") (pinfunction "SW-R_SW-R") (pintype "bidirectional"))
    )
  )
)
